# ADC.net
KiCad netlist of a schematic drawn in EAGLE
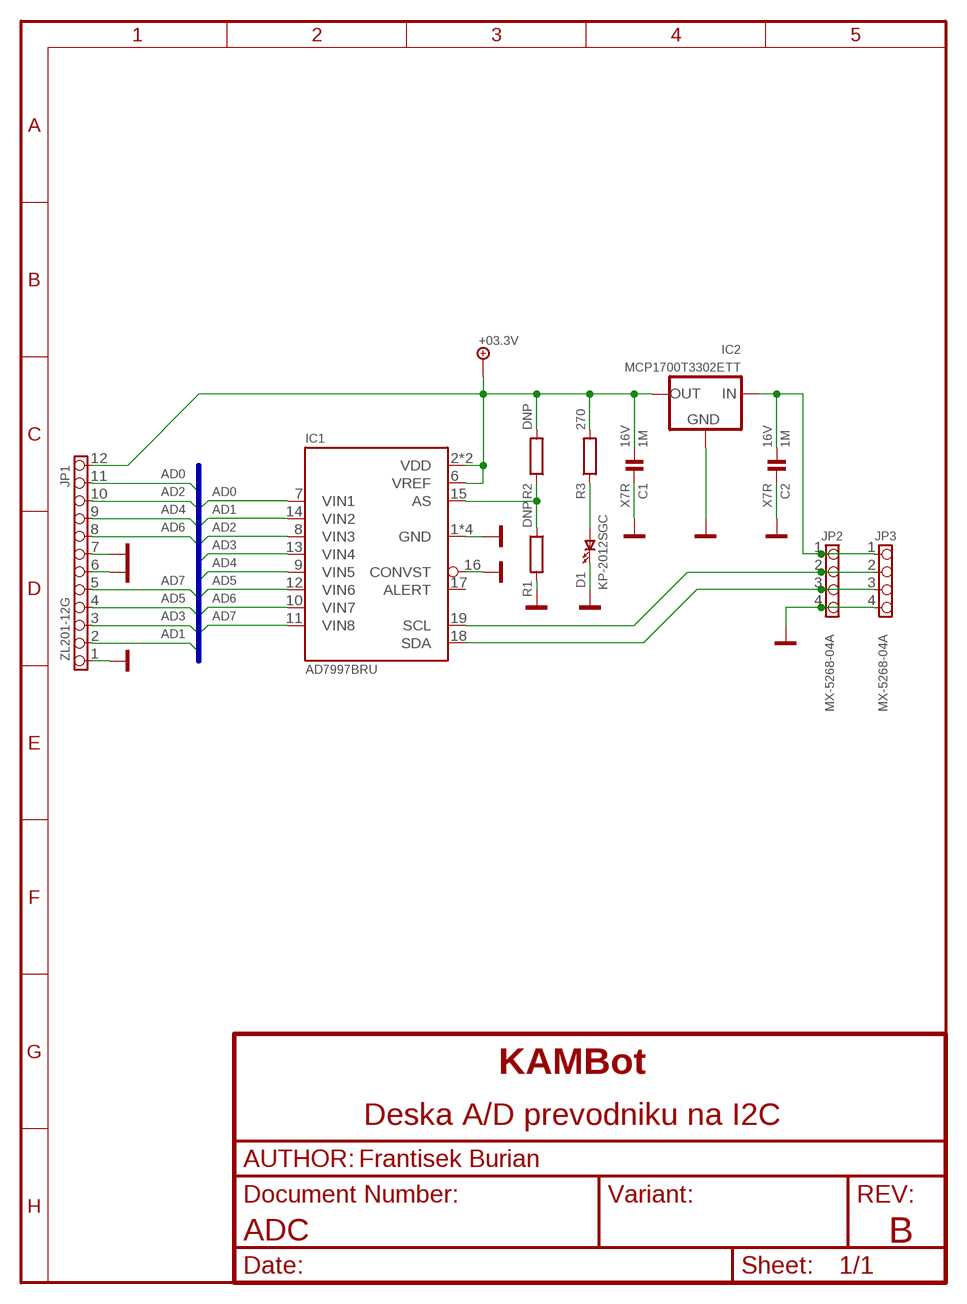
[diagram p0: schematic, sheet 1]

(export (version "E")
  (design (tool "Eeschema 10.0.6"))
  (components
    (comp (ref "C1")
      (value "1M")
      (footprint "eagle-import:0805")
      (fields (field (name "VOLTAGE") "16V"))
      (libsource (lib "eagle-import") (part "C0805"))
    )
    (comp (ref "C2")
      (value "1M")
      (footprint "eagle-import:0805")
      (fields (field (name "VOLTAGE") "16V"))
      (libsource (lib "eagle-import") (part "C0805"))
    )
    (comp (ref "D1")
      (value "KP-2012SGC")
      (footprint "eagle-import:LED_0805")
      (libsource (lib "eagle-import") (part "LED0805"))
    )
    (comp (ref "IC1")
      (value "AD7997BRU")
      (footprint "eagle-import:TSSOP20")
      (libsource (lib "eagle-import") (part "AD7997BRU"))
    )
    (comp (ref "IC2")
      (value "MCP1700T3302ETT")
      (footprint "eagle-import:SOT23")
      (libsource (lib "eagle-import") (part "MCP1700"))
    )
    (comp (ref "JP1")
      (value "ZL201-12G")
      (footprint "eagle-import:1X12_254_EDGE")
      (libsource (lib "eagle-import") (part "PINHD-1X12_254_EDGE"))
    )
    (comp (ref "JP2")
      (value "MX-5268-04A")
      (footprint "eagle-import:1X04_250_MX5268")
      (libsource (lib "eagle-import") (part "PINHD-1X4_250_MX5268"))
    )
    (comp (ref "JP3")
      (value "MX-5268-04A")
      (footprint "eagle-import:1X04_250_MX5268")
      (libsource (lib "eagle-import") (part "PINHD-1X4_250_MX5268"))
    )
    (comp (ref "R1")
      (value "DNP")
      (footprint "eagle-import:0805")
      (libsource (lib "eagle-import") (part "R_R0805"))
    )
    (comp (ref "R2")
      (value "DNP")
      (footprint "eagle-import:0805")
      (libsource (lib "eagle-import") (part "R_R0805"))
    )
    (comp (ref "R3")
      (value "270")
      (footprint "eagle-import:0805")
      (libsource (lib "eagle-import") (part "R_R0805"))
    )
  )
  (nets
    (net (code "1") (name "+03.3V") (class "Default")
      (node (ref "C1") (pin "2") (pinfunction "2_2") (pintype "passive"))
      (node (ref "IC1") (pin "2") (pinfunction "VDD_2") (pintype "passive"))
      (node (ref "IC1") (pin "5") (pinfunction "VDD_5") (pintype "passive"))
      (node (ref "IC1") (pin "6") (pinfunction "VREF_6") (pintype "passive"))
      (node (ref "IC2") (pin "2") (pinfunction "OUT_2") (pintype "passive"))
      (node (ref "JP1") (pin "12") (pinfunction "12_12") (pintype "passive"))
      (node (ref "R2") (pin "2") (pinfunction "2_2") (pintype "passive"))
      (node (ref "R3") (pin "2") (pinfunction "2_2") (pintype "passive"))
    )
    (net (code "2") (name "/AD0") (class "Default")
      (node (ref "IC1") (pin "7") (pinfunction "VIN1_7") (pintype "passive"))
      (node (ref "JP1") (pin "11") (pinfunction "11_11") (pintype "passive"))
    )
    (net (code "3") (name "/AD1") (class "Default")
      (node (ref "IC1") (pin "14") (pinfunction "VIN2_14") (pintype "passive"))
      (node (ref "JP1") (pin "2") (pinfunction "2_2") (pintype "passive"))
    )
    (net (code "4") (name "/AD2") (class "Default")
      (node (ref "IC1") (pin "8") (pinfunction "VIN3_8") (pintype "passive"))
      (node (ref "JP1") (pin "10") (pinfunction "10_10") (pintype "passive"))
    )
    (net (code "5") (name "/AD3") (class "Default")
      (node (ref "IC1") (pin "13") (pinfunction "VIN4_13") (pintype "passive"))
      (node (ref "JP1") (pin "3") (pinfunction "3_3") (pintype "passive"))
    )
    (net (code "6") (name "/AD4") (class "Default")
      (node (ref "IC1") (pin "9") (pinfunction "VIN5_9") (pintype "passive"))
      (node (ref "JP1") (pin "9") (pinfunction "9_9") (pintype "passive"))
    )
    (net (code "7") (name "/AD5") (class "Default")
      (node (ref "IC1") (pin "12") (pinfunction "VIN6_12") (pintype "passive"))
      (node (ref "JP1") (pin "4") (pinfunction "4_4") (pintype "passive"))
    )
    (net (code "8") (name "/AD6") (class "Default")
      (node (ref "IC1") (pin "10") (pinfunction "VIN7_10") (pintype "passive"))
      (node (ref "JP1") (pin "8") (pinfunction "8_8") (pintype "passive"))
    )
    (net (code "9") (name "/AD7") (class "Default")
      (node (ref "IC1") (pin "11") (pinfunction "VIN8_11") (pintype "passive"))
      (node (ref "JP1") (pin "5") (pinfunction "5_5") (pintype "passive"))
    )
    (net (code "10") (name "GND") (class "Default")
      (node (ref "C1") (pin "1") (pinfunction "1_1") (pintype "passive"))
      (node (ref "C2") (pin "1") (pinfunction "1_1") (pintype "passive"))
      (node (ref "D1") (pin "K") (pinfunction "C_K") (pintype "passive"))
      (node (ref "IC1") (pin "1") (pinfunction "GND_1") (pintype "passive"))
      (node (ref "IC1") (pin "16") (pinfunction "CONVST_16") (pintype "passive"))
      (node (ref "IC1") (pin "20") (pinfunction "GND_20") (pintype "passive"))
      (node (ref "IC1") (pin "3") (pinfunction "GND_3") (pintype "passive"))
      (node (ref "IC1") (pin "4") (pinfunction "GND_4") (pintype "passive"))
      (node (ref "IC2") (pin "1") (pinfunction "GND_1") (pintype "passive"))
      (node (ref "JP1") (pin "1") (pinfunction "1_1") (pintype "passive"))
      (node (ref "JP1") (pin "6") (pinfunction "6_6") (pintype "passive"))
      (node (ref "JP1") (pin "7") (pinfunction "7_7") (pintype "passive"))
      (node (ref "JP2") (pin "4") (pinfunction "4_4") (pintype "passive"))
      (node (ref "JP3") (pin "4") (pinfunction "4_4") (pintype "passive"))
      (node (ref "R1") (pin "2") (pinfunction "2_2") (pintype "passive"))
    )
    (net (code "11") (name "Net-(D1-PadA)") (class "Default")
      (node (ref "D1") (pin "A") (pinfunction "A_A") (pintype "passive"))
      (node (ref "R3") (pin "1") (pinfunction "1_1") (pintype "passive"))
    )
    (net (code "12") (name "Net-(IC1-AS)") (class "Default")
      (node (ref "IC1") (pin "15") (pinfunction "AS_15") (pintype "passive"))
      (node (ref "R1") (pin "1") (pinfunction "1_1") (pintype "passive"))
      (node (ref "R2") (pin "1") (pinfunction "1_1") (pintype "passive"))
    )
    (net (code "13") (name "Net-(IC1-SCL)") (class "Default")
      (node (ref "IC1") (pin "19") (pinfunction "SCL_19") (pintype "passive"))
      (node (ref "JP2") (pin "2") (pinfunction "2_2") (pintype "passive"))
      (node (ref "JP3") (pin "2") (pinfunction "2_2") (pintype "passive"))
    )
    (net (code "14") (name "Net-(IC1-SDA)") (class "Default")
      (node (ref "IC1") (pin "18") (pinfunction "SDA_18") (pintype "passive"))
      (node (ref "JP2") (pin "3") (pinfunction "3_3") (pintype "passive"))
      (node (ref "JP3") (pin "3") (pinfunction "3_3") (pintype "passive"))
    )
    (net (code "15") (name "Net-(IC2-IN)") (class "Default")
      (node (ref "C2") (pin "2") (pinfunction "2_2") (pintype "passive"))
      (node (ref "IC2") (pin "3") (pinfunction "IN_3") (pintype "passive"))
      (node (ref "JP2") (pin "1") (pinfunction "1_1") (pintype "passive"))
      (node (ref "JP3") (pin "1") (pinfunction "1_1") (pintype "passive"))
    )
    (net (code "16") (name "unconnected-(IC1-ALERT-Pad17)") (class "Default")
      (node (ref "IC1") (pin "17") (pinfunction "ALERT_17") (pintype "passive"))
    )
  )
)
